# Raincenter_APP-TS_ARM_ISO_0_01.net
KiCad netlist of a schematic drawn in EAGLE
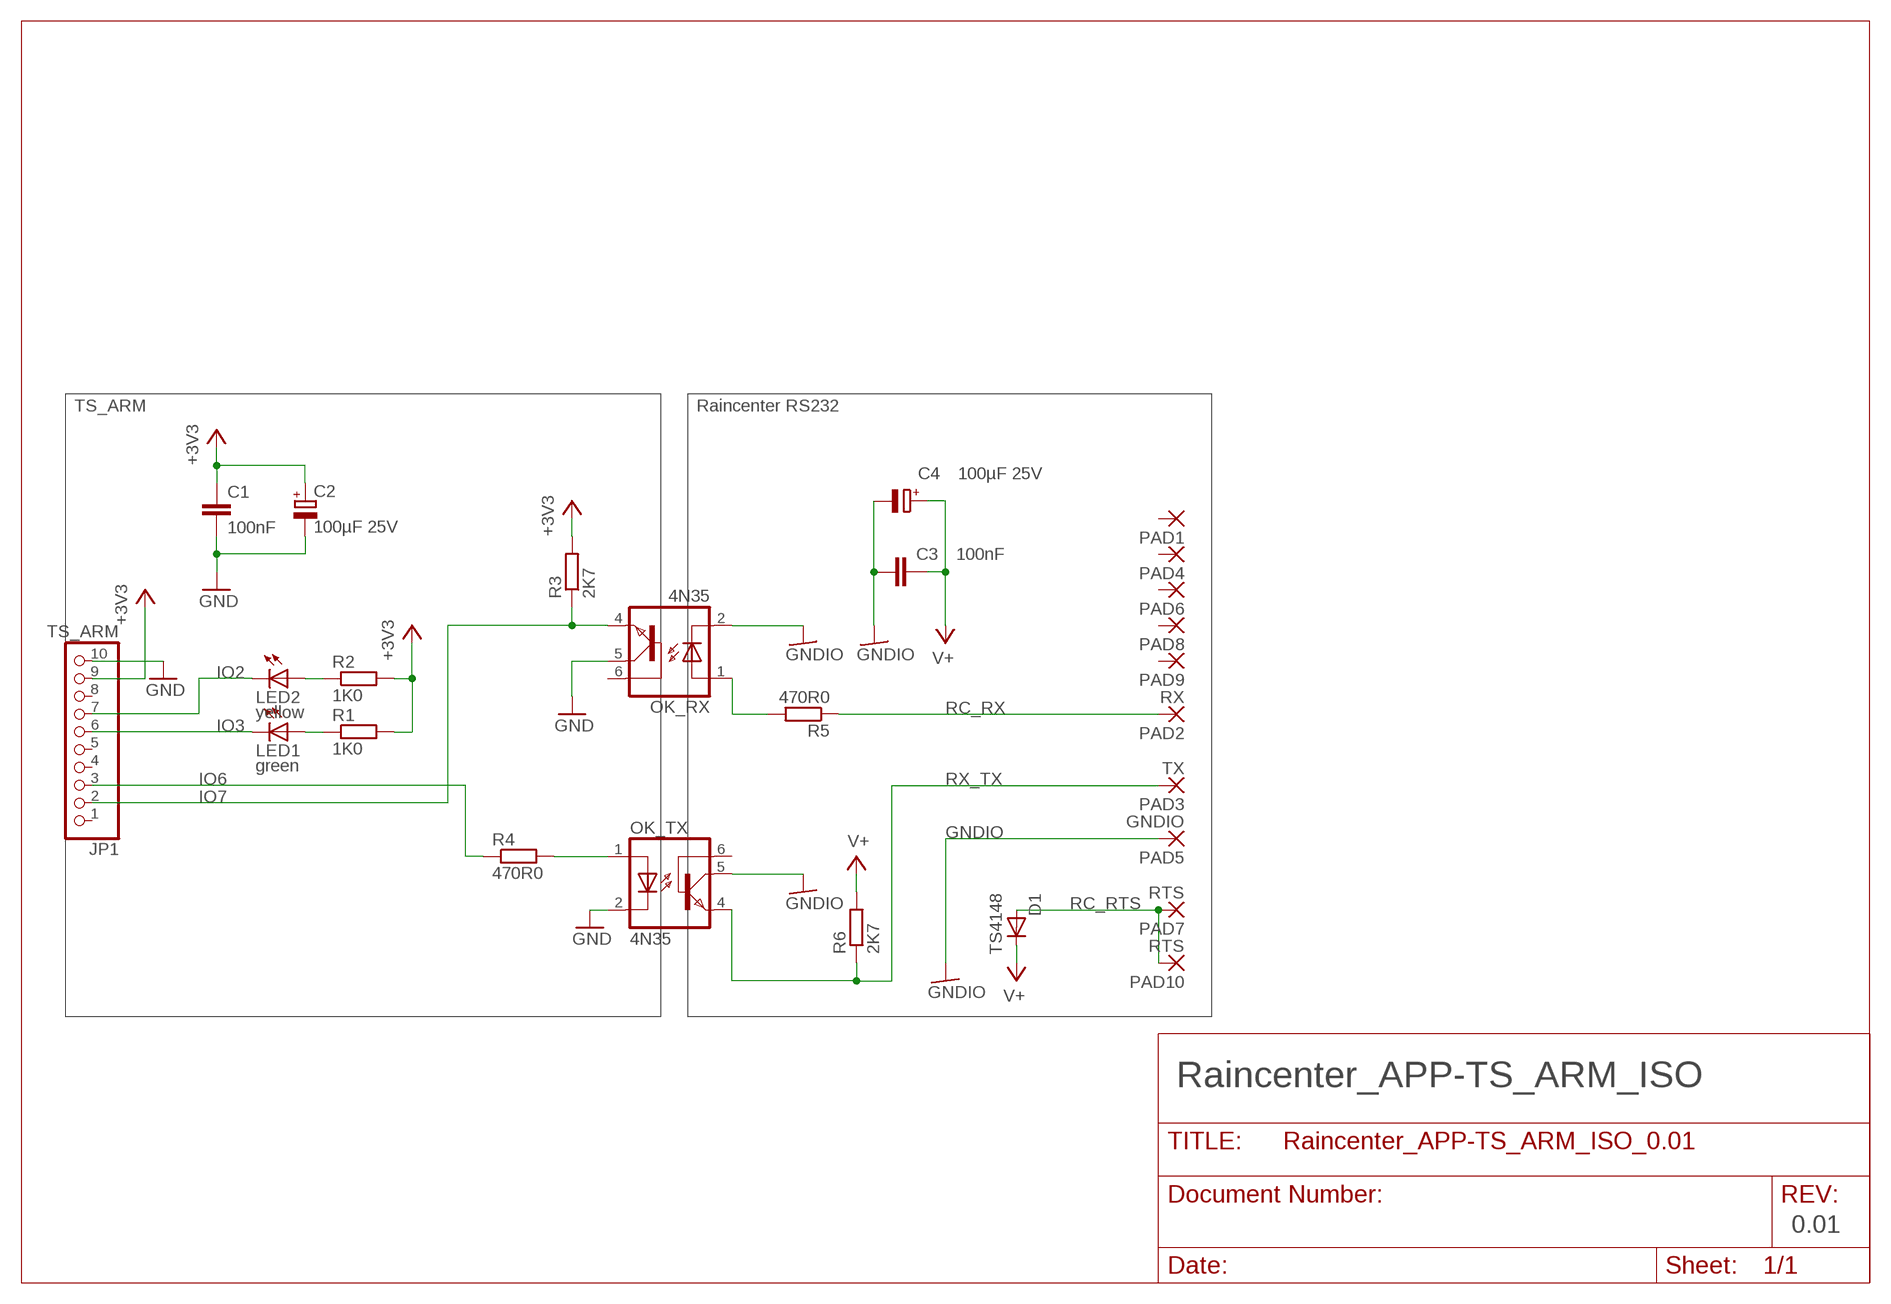
[diagram p0: schematic, sheet 1]

(export (version "E")
  (design (tool "Eeschema 10.0.6"))
  (components
    (comp (ref "C1")
      (value "100nF")
      (footprint "eagle-import:C1206K")
      (libsource (lib "eagle-import") (part "C-EUC1206K"))
    )
    (comp (ref "C2")
      (value "100µF 25V")
      (footprint "eagle-import:PANASONIC_D")
      (libsource (lib "eagle-import") (part "CPOL-EUD"))
    )
    (comp (ref "C3")
      (value "100nF")
      (footprint "eagle-import:C1206K")
      (libsource (lib "eagle-import") (part "C-EUC1206K"))
    )
    (comp (ref "C4")
      (value "100µF 25V")
      (footprint "eagle-import:PANASONIC_D")
      (libsource (lib "eagle-import") (part "CPOL-EUD"))
    )
    (comp (ref "D1")
      (value "TS4148")
      (footprint "eagle-import:1206")
      (libsource (lib "eagle-import") (part "TS4148"))
    )
    (comp (ref "JP1")
      (value "TS_ARM")
      (footprint "eagle-import:1X10")
      (libsource (lib "eagle-import") (part "PINHD-1X10"))
    )
    (comp (ref "LED1")
      (value "green")
      (footprint "eagle-import:CHIPLED_1206")
      (libsource (lib "eagle-import") (part "LEDCHIPLED_1206"))
    )
    (comp (ref "LED2")
      (value "yellow")
      (footprint "eagle-import:CHIPLED_1206")
      (libsource (lib "eagle-import") (part "LEDCHIPLED_1206"))
    )
    (comp (ref "OK_RX")
      (value "4N35")
      (footprint "eagle-import:DIL06")
      (fields (field (name "MF") "FAIRCHILD SEMICONDUCTOR"))
      (libsource (lib "eagle-import") (part "4N35"))
    )
    (comp (ref "OK_TX")
      (value "4N35")
      (footprint "eagle-import:DIL06")
      (fields (field (name "MF") "FAIRCHILD SEMICONDUCTOR"))
      (libsource (lib "eagle-import") (part "4N35"))
    )
    (comp (ref "PAD1")
      (value "WIREPADSMD1,27-254")
      (footprint "eagle-import:SMD1,27-2,54")
      (libsource (lib "eagle-import") (part "WIREPADSMD1,27-254"))
    )
    (comp (ref "PAD2")
      (value "RX")
      (footprint "eagle-import:SMD1,27-2,54")
      (libsource (lib "eagle-import") (part "WIREPADSMD1,27-254"))
    )
    (comp (ref "PAD3")
      (value "TX")
      (footprint "eagle-import:SMD1,27-2,54")
      (libsource (lib "eagle-import") (part "WIREPADSMD1,27-254"))
    )
    (comp (ref "PAD4")
      (value "WIREPADSMD1,27-254")
      (footprint "eagle-import:SMD1,27-2,54")
      (libsource (lib "eagle-import") (part "WIREPADSMD1,27-254"))
    )
    (comp (ref "PAD5")
      (value "GNDIO")
      (footprint "eagle-import:SMD1,27-2,54")
      (libsource (lib "eagle-import") (part "WIREPADSMD1,27-254"))
    )
    (comp (ref "PAD6")
      (value "WIREPADSMD1,27-254")
      (footprint "eagle-import:SMD1,27-2,54")
      (libsource (lib "eagle-import") (part "WIREPADSMD1,27-254"))
    )
    (comp (ref "PAD7")
      (value "RTS")
      (footprint "eagle-import:SMD1,27-2,54")
      (libsource (lib "eagle-import") (part "WIREPADSMD1,27-254"))
    )
    (comp (ref "PAD8")
      (value "WIREPADSMD1,27-254")
      (footprint "eagle-import:SMD1,27-2,54")
      (libsource (lib "eagle-import") (part "WIREPADSMD1,27-254"))
    )
    (comp (ref "PAD9")
      (value "WIREPADSMD1,27-254")
      (footprint "eagle-import:SMD1,27-2,54")
      (libsource (lib "eagle-import") (part "WIREPADSMD1,27-254"))
    )
    (comp (ref "PAD10")
      (value "RTS")
      (footprint "eagle-import:SMD1,27-2,54")
      (libsource (lib "eagle-import") (part "WIREPADSMD1,27-254"))
    )
    (comp (ref "R1")
      (value "1K0")
      (footprint "eagle-import:R1206")
      (libsource (lib "eagle-import") (part "R-EU_R1206"))
    )
    (comp (ref "R2")
      (value "1K0")
      (footprint "eagle-import:R1206")
      (libsource (lib "eagle-import") (part "R-EU_R1206"))
    )
    (comp (ref "R3")
      (value "2K7")
      (footprint "eagle-import:R1206")
      (libsource (lib "eagle-import") (part "R-EU_R1206"))
    )
    (comp (ref "R4")
      (value "470R0")
      (footprint "eagle-import:R1206")
      (libsource (lib "eagle-import") (part "R-EU_R1206"))
    )
    (comp (ref "R5")
      (value "470R0")
      (footprint "eagle-import:R1206")
      (libsource (lib "eagle-import") (part "R-EU_R1206"))
    )
    (comp (ref "R6")
      (value "2K7")
      (footprint "eagle-import:R1206")
      (libsource (lib "eagle-import") (part "R-EU_R1206"))
    )
  )
  (nets
    (net (code "1") (name "+3V3") (class "Default")
      (node (ref "C1") (pin "1") (pinfunction "1_1") (pintype "passive"))
      (node (ref "C2") (pin "+") (pinfunction "+_+") (pintype "passive"))
      (node (ref "JP1") (pin "9") (pinfunction "9_9") (pintype "passive"))
      (node (ref "R1") (pin "2") (pinfunction "2_2") (pintype "passive"))
      (node (ref "R2") (pin "2") (pinfunction "2_2") (pintype "passive"))
      (node (ref "R3") (pin "2") (pinfunction "2_2") (pintype "passive"))
    )
    (net (code "2") (name "/IO2") (class "Default")
      (node (ref "JP1") (pin "7") (pinfunction "7_7") (pintype "passive"))
      (node (ref "LED2") (pin "C") (pinfunction "C_C") (pintype "passive"))
    )
    (net (code "3") (name "/IO3") (class "Default")
      (node (ref "JP1") (pin "6") (pinfunction "6_6") (pintype "passive"))
      (node (ref "LED1") (pin "C") (pinfunction "C_C") (pintype "passive"))
    )
    (net (code "4") (name "/IO6") (class "Default")
      (node (ref "JP1") (pin "3") (pinfunction "3_3") (pintype "passive"))
      (node (ref "R4") (pin "1") (pinfunction "1_1") (pintype "passive"))
    )
    (net (code "5") (name "/IO7") (class "Default")
      (node (ref "JP1") (pin "2") (pinfunction "2_2") (pintype "passive"))
      (node (ref "OK_RX") (pin "4") (pinfunction "EMI_4") (pintype "passive"))
      (node (ref "R3") (pin "1") (pinfunction "1_1") (pintype "passive"))
    )
    (net (code "6") (name "/RC_RTS") (class "Default")
      (node (ref "D1") (pin "ANODE") (pinfunction "A_ANODE") (pintype "passive"))
      (node (ref "PAD10") (pin "1") (pinfunction "P_1") (pintype "passive"))
      (node (ref "PAD7") (pin "1") (pinfunction "P_1") (pintype "passive"))
    )
    (net (code "7") (name "/RC_RX") (class "Default")
      (node (ref "PAD2") (pin "1") (pinfunction "P_1") (pintype "passive"))
      (node (ref "R5") (pin "1") (pinfunction "1_1") (pintype "passive"))
    )
    (net (code "8") (name "/RX_TX") (class "Default")
      (node (ref "OK_TX") (pin "4") (pinfunction "EMI_4") (pintype "passive"))
      (node (ref "PAD3") (pin "1") (pinfunction "P_1") (pintype "passive"))
      (node (ref "R6") (pin "1") (pinfunction "1_1") (pintype "passive"))
    )
    (net (code "9") (name "GND") (class "Default")
      (node (ref "C1") (pin "2") (pinfunction "2_2") (pintype "passive"))
      (node (ref "C2") (pin "-") (pinfunction "-_-") (pintype "passive"))
      (node (ref "JP1") (pin "10") (pinfunction "10_10") (pintype "passive"))
      (node (ref "OK_RX") (pin "5") (pinfunction "COL_5") (pintype "passive"))
      (node (ref "OK_TX") (pin "2") (pinfunction "C_2") (pintype "passive"))
    )
    (net (code "10") (name "GNDIO") (class "Default")
      (node (ref "C3") (pin "2") (pinfunction "2_2") (pintype "passive"))
      (node (ref "C4") (pin "-") (pinfunction "-_-") (pintype "passive"))
      (node (ref "OK_RX") (pin "2") (pinfunction "C_2") (pintype "passive"))
      (node (ref "OK_TX") (pin "5") (pinfunction "COL_5") (pintype "passive"))
      (node (ref "PAD5") (pin "1") (pinfunction "P_1") (pintype "passive"))
    )
    (net (code "11") (name "Net-(LED1-PadA)") (class "Default")
      (node (ref "LED1") (pin "A") (pinfunction "A_A") (pintype "passive"))
      (node (ref "R1") (pin "1") (pinfunction "1_1") (pintype "passive"))
    )
    (net (code "12") (name "Net-(LED2-PadA)") (class "Default")
      (node (ref "LED2") (pin "A") (pinfunction "A_A") (pintype "passive"))
      (node (ref "R2") (pin "1") (pinfunction "1_1") (pintype "passive"))
    )
    (net (code "13") (name "Net-(OK_RX-A)") (class "Default")
      (node (ref "OK_RX") (pin "1") (pinfunction "A_1") (pintype "passive"))
      (node (ref "R5") (pin "2") (pinfunction "2_2") (pintype "passive"))
    )
    (net (code "14") (name "Net-(OK_TX-A)") (class "Default")
      (node (ref "OK_TX") (pin "1") (pinfunction "A_1") (pintype "passive"))
      (node (ref "R4") (pin "2") (pinfunction "2_2") (pintype "passive"))
    )
    (net (code "15") (name "V+") (class "Default")
      (node (ref "C3") (pin "1") (pinfunction "1_1") (pintype "passive"))
      (node (ref "C4") (pin "+") (pinfunction "+_+") (pintype "passive"))
      (node (ref "D1") (pin "KATHODE") (pinfunction "K_KATHODE") (pintype "passive"))
      (node (ref "R6") (pin "2") (pinfunction "2_2") (pintype "passive"))
    )
    (net (code "16") (name "unconnected-(JP1-Pad1)") (class "Default")
      (node (ref "JP1") (pin "1") (pinfunction "1_1") (pintype "passive"))
    )
    (net (code "17") (name "unconnected-(JP1-Pad4)") (class "Default")
      (node (ref "JP1") (pin "4") (pinfunction "4_4") (pintype "passive"))
    )
    (net (code "18") (name "unconnected-(JP1-Pad5)") (class "Default")
      (node (ref "JP1") (pin "5") (pinfunction "5_5") (pintype "passive"))
    )
    (net (code "19") (name "unconnected-(JP1-Pad8)") (class "Default")
      (node (ref "JP1") (pin "8") (pinfunction "8_8") (pintype "passive"))
    )
    (net (code "20") (name "unconnected-(OK_RX-BAS-Pad6)") (class "Default")
      (node (ref "OK_RX") (pin "6") (pinfunction "BAS_6") (pintype "passive"))
    )
    (net (code "21") (name "unconnected-(OK_TX-BAS-Pad6)") (class "Default")
      (node (ref "OK_TX") (pin "6") (pinfunction "BAS_6") (pintype "passive"))
    )
    (net (code "22") (name "unconnected-(PAD1-P-Pad1)") (class "Default")
      (node (ref "PAD1") (pin "1") (pinfunction "P_1") (pintype "passive"))
    )
    (net (code "23") (name "unconnected-(PAD4-P-Pad1)") (class "Default")
      (node (ref "PAD4") (pin "1") (pinfunction "P_1") (pintype "passive"))
    )
    (net (code "24") (name "unconnected-(PAD6-P-Pad1)") (class "Default")
      (node (ref "PAD6") (pin "1") (pinfunction "P_1") (pintype "passive"))
    )
    (net (code "25") (name "unconnected-(PAD8-P-Pad1)") (class "Default")
      (node (ref "PAD8") (pin "1") (pinfunction "P_1") (pintype "passive"))
    )
    (net (code "26") (name "unconnected-(PAD9-P-Pad1)") (class "Default")
      (node (ref "PAD9") (pin "1") (pinfunction "P_1") (pintype "passive"))
    )
  )
)
